# LED_Board.net
KiCad netlist of a schematic drawn in EAGLE
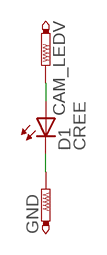
[diagram p0: schematic, sheet 1]

(export (version "E")
  (design (tool "Eeschema 10.0.6"))
  (components
    (comp (ref "CAM_LEDV")
      (value "PTR1PAD1-20")
      (footprint "eagle-import:P1-20")
      (libsource (lib "eagle-import") (part "PTR1PAD1-20"))
    )
    (comp (ref "D1")
      (value "CREE")
      (footprint "eagle-import:CREE-XLAMP-XM-L")
      (libsource (lib "eagle-import") (part "CREE"))
    )
    (comp (ref "GND")
      (value "PTR1PAD1-20")
      (footprint "eagle-import:P1-20")
      (libsource (lib "eagle-import") (part "PTR1PAD1-20"))
    )
  )
  (nets
    (net (code "1") (name "Net-(CAM_LEDV-PadTP)") (class "Default")
      (node (ref "CAM_LEDV") (pin "TP") (pinfunction "TP_TP") (pintype "input"))
      (node (ref "D1") (pin "A") (pinfunction "A_A") (pintype "input"))
      (node (ref "D1") (pin "A@1") (pinfunction "A_A@1") (pintype "input"))
    )
    (net (code "2") (name "Net-(D1-C-PadC1)") (class "Default")
      (node (ref "D1") (pin "C") (pinfunction "C_C") (pintype "output"))
      (node (ref "D1") (pin "C1") (pinfunction "C_C1") (pintype "output"))
      (node (ref "D1") (pin "C@1") (pinfunction "C_C@1") (pintype "output"))
      (node (ref "GND") (pin "TP") (pinfunction "TP_TP") (pintype "input"))
    )
  )
)
